# tinyek.net
KiCad netlist of a schematic drawn in EAGLE
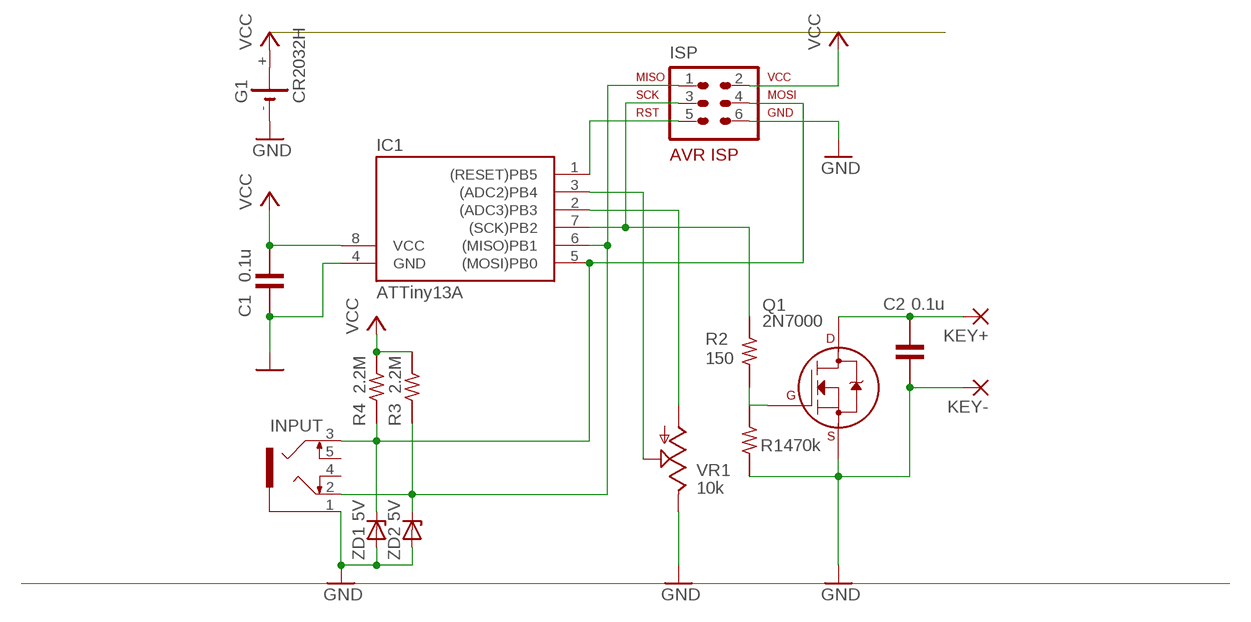
[diagram p0: schematic, sheet 1]

(export (version "E")
  (design (tool "Eeschema 10.0.6"))
  (components
    (comp (ref "C1")
      (value "0.1u")
      (footprint "eagle-import:50-0302-5.08")
      (libsource (lib "eagle-import") (part "C-50V-0302-5.08"))
    )
    (comp (ref "C2")
      (value "0.1u")
      (footprint "eagle-import:50-0302-5.08")
      (libsource (lib "eagle-import") (part "C-50V-0302-5.08"))
    )
    (comp (ref "G1")
      (value "CR2032H")
      (footprint "eagle-import:CR2032H")
      (libsource (lib "eagle-import") (part "CR2032H"))
    )
    (comp (ref "IC1")
      (value "ATTiny13A")
      (footprint "eagle-import:DIL08")
      (libsource (lib "eagle-import") (part "TINY138P3"))
    )
    (comp (ref "INPUT")
      (value "1503_09")
      (footprint "eagle-import:1503_09")
      (libsource (lib "eagle-import") (part "1503_09"))
    )
    (comp (ref "ISP")
      (value "AVR-ISP-6VERT")
      (footprint "eagle-import:AVR-ISP-6")
      (libsource (lib "eagle-import") (part "AVR-ISP-6VERT"))
    )
    (comp (ref "KEY+")
      (value "2,15/1,0")
      (footprint "eagle-import:2,15_1,0")
      (libsource (lib "eagle-import") (part "2,15/1,0"))
    )
    (comp (ref "KEY-")
      (value "2,15/1,0")
      (footprint "eagle-import:2,15_1,0")
      (libsource (lib "eagle-import") (part "2,15/1,0"))
    )
    (comp (ref "Q1")
      (value "2N7000")
      (footprint "eagle-import:TO-92")
      (libsource (lib "eagle-import") (part "2N700_TO920"))
    )
    (comp (ref "R1")
      (value "470k")
      (footprint "eagle-import:1_4W-2.54V")
      (libsource (lib "eagle-import") (part "R-1/4W-02.54-V"))
    )
    (comp (ref "R2")
      (value "150")
      (footprint "eagle-import:1_4W-2.54V")
      (libsource (lib "eagle-import") (part "R-1/4W-02.54-V"))
    )
    (comp (ref "R3")
      (value "2.2M")
      (footprint "eagle-import:1_4W-7.62H")
      (libsource (lib "eagle-import") (part "R-1/4W-07.62"))
    )
    (comp (ref "R4")
      (value "2.2M")
      (footprint "eagle-import:1_4W-7.62H")
      (libsource (lib "eagle-import") (part "R-1/4W-07.62"))
    )
    (comp (ref "VR1")
      (value "10k")
      (footprint "eagle-import:B25U")
      (libsource (lib "eagle-import") (part "TRIM_US-B25U"))
    )
    (comp (ref "ZD1")
      (value "5V")
      (footprint "eagle-import:DO35Z10")
      (libsource (lib "eagle-import") (part "ZPD"))
    )
    (comp (ref "ZD2")
      (value "5V")
      (footprint "eagle-import:DO35Z10")
      (libsource (lib "eagle-import") (part "ZPD"))
    )
  )
  (nets
    (net (code "1") (name "GND") (class "Default")
      (node (ref "C1") (pin "PAD1") (pinfunction "1_PAD1") (pintype "passive"))
      (node (ref "C2") (pin "PAD2") (pinfunction "2_PAD2") (pintype "passive"))
      (node (ref "G1") (pin "-") (pinfunction "-_-") (pintype "passive"))
      (node (ref "IC1") (pin "4") (pinfunction "GND_4") (pintype "power_in"))
      (node (ref "INPUT") (pin "1") (pinfunction "1_1") (pintype "passive"))
      (node (ref "ISP") (pin "6") (pinfunction "6_6") (pintype "passive"))
      (node (ref "KEY-") (pin "1") (pinfunction "P_1") (pintype "passive"))
      (node (ref "Q1") (pin "1") (pinfunction "S_1") (pintype "bidirectional"))
      (node (ref "R1") (pin "PAD2") (pinfunction "2_PAD2") (pintype "passive"))
      (node (ref "VR1") (pin "E") (pinfunction "E_E") (pintype "passive"))
      (node (ref "ZD1") (pin "A") (pinfunction "A_A") (pintype "passive"))
      (node (ref "ZD2") (pin "A") (pinfunction "A_A") (pintype "passive"))
    )
    (net (code "2") (name "Net-(C2-1)") (class "Default")
      (node (ref "C2") (pin "PAD1") (pinfunction "1_PAD1") (pintype "passive"))
      (node (ref "KEY+") (pin "1") (pinfunction "P_1") (pintype "passive"))
      (node (ref "Q1") (pin "3") (pinfunction "D_3") (pintype "bidirectional"))
    )
    (net (code "3") (name "Net-(IC1-(ADC2)PB4)") (class "Default")
      (node (ref "IC1") (pin "3") (pinfunction "(ADC2)PB4_3") (pintype "bidirectional"))
      (node (ref "VR1") (pin "S") (pinfunction "S_S") (pintype "passive"))
    )
    (net (code "4") (name "Net-(IC1-(ADC3)PB3)") (class "Default")
      (node (ref "IC1") (pin "2") (pinfunction "(ADC3)PB3_2") (pintype "bidirectional"))
      (node (ref "VR1") (pin "A") (pinfunction "A_A") (pintype "passive"))
    )
    (net (code "5") (name "Net-(IC1-(MISO)PB1)") (class "Default")
      (node (ref "IC1") (pin "6") (pinfunction "(MISO)PB1_6") (pintype "bidirectional"))
      (node (ref "INPUT") (pin "2") (pinfunction "2_2") (pintype "passive"))
      (node (ref "ISP") (pin "1") (pinfunction "1_1") (pintype "passive"))
      (node (ref "R3") (pin "PAD2") (pinfunction "2_PAD2") (pintype "passive"))
      (node (ref "ZD2") (pin "C") (pinfunction "C_C") (pintype "passive"))
    )
    (net (code "6") (name "Net-(IC1-(MOSI)PB0)") (class "Default")
      (node (ref "IC1") (pin "5") (pinfunction "(MOSI)PB0_5") (pintype "bidirectional"))
      (node (ref "INPUT") (pin "3") (pinfunction "3_3") (pintype "passive"))
      (node (ref "ISP") (pin "4") (pinfunction "4_4") (pintype "passive"))
      (node (ref "R4") (pin "PAD2") (pinfunction "2_PAD2") (pintype "passive"))
      (node (ref "ZD1") (pin "C") (pinfunction "C_C") (pintype "passive"))
    )
    (net (code "7") (name "Net-(IC1-(RESET)PB5)") (class "Default")
      (node (ref "IC1") (pin "1") (pinfunction "(RESET)PB5_1") (pintype "bidirectional"))
      (node (ref "ISP") (pin "5") (pinfunction "5_5") (pintype "passive"))
    )
    (net (code "8") (name "Net-(IC1-(SCK)PB2)") (class "Default")
      (node (ref "IC1") (pin "7") (pinfunction "(SCK)PB2_7") (pintype "bidirectional"))
      (node (ref "ISP") (pin "3") (pinfunction "3_3") (pintype "passive"))
      (node (ref "R2") (pin "PAD1") (pinfunction "1_PAD1") (pintype "passive"))
    )
    (net (code "9") (name "Net-(Q1-G)") (class "Default")
      (node (ref "Q1") (pin "2") (pinfunction "G_2") (pintype "tri_state"))
      (node (ref "R1") (pin "PAD1") (pinfunction "1_PAD1") (pintype "passive"))
      (node (ref "R2") (pin "PAD2") (pinfunction "2_PAD2") (pintype "passive"))
    )
    (net (code "10") (name "VCC") (class "Default")
      (node (ref "C1") (pin "PAD2") (pinfunction "2_PAD2") (pintype "passive"))
      (node (ref "G1") (pin "+") (pinfunction "+_+") (pintype "passive"))
      (node (ref "IC1") (pin "8") (pinfunction "VCC_8") (pintype "power_in"))
      (node (ref "ISP") (pin "2") (pinfunction "2_2") (pintype "passive"))
      (node (ref "R3") (pin "PAD1") (pinfunction "1_PAD1") (pintype "passive"))
      (node (ref "R4") (pin "PAD1") (pinfunction "1_PAD1") (pintype "passive"))
    )
    (net (code "11") (name "unconnected-(G1-+-Pad+@1)") (class "Default")
      (node (ref "G1") (pin "+@1") (pinfunction "+_+@1") (pintype "passive"))
    )
    (net (code "12") (name "unconnected-(INPUT-Pad4)") (class "Default")
      (node (ref "INPUT") (pin "4") (pinfunction "4_4") (pintype "passive"))
    )
    (net (code "13") (name "unconnected-(INPUT-Pad5)") (class "Default")
      (node (ref "INPUT") (pin "5") (pinfunction "5_5") (pintype "passive"))
    )
  )
)
